# Flightcontroller.net
KiCad netlist of a schematic drawn in EAGLE
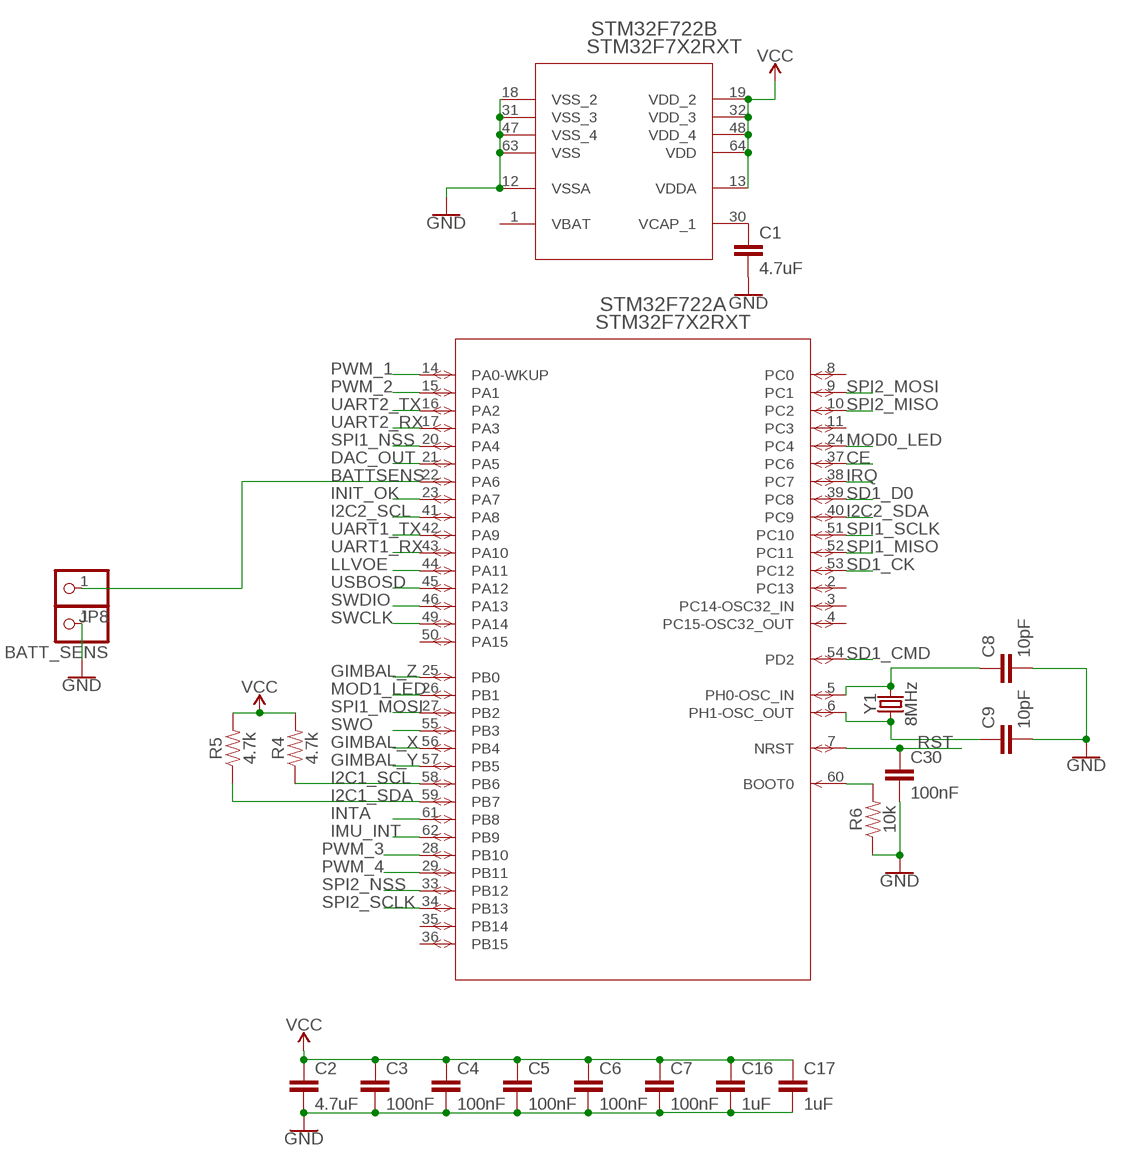
[diagram p0: schematic, sheet 1]
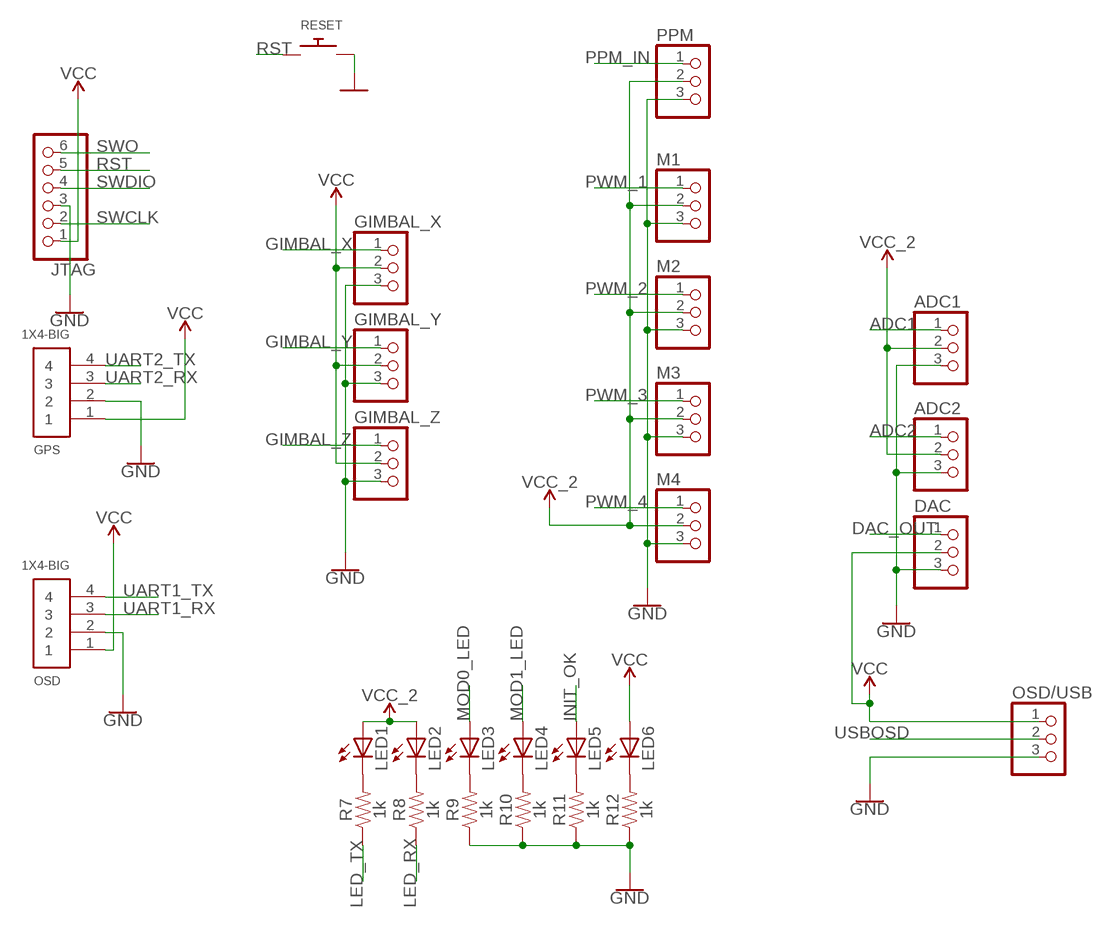
[diagram p1: schematic, sheet 2]
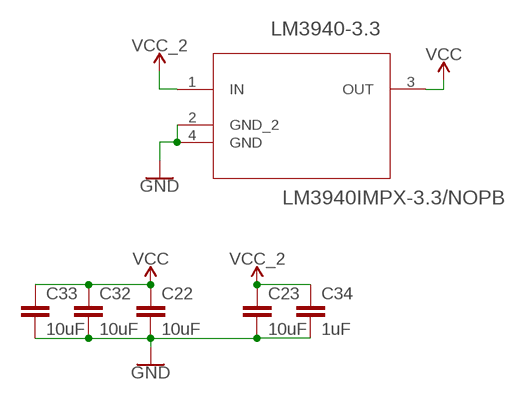
[diagram p2: schematic, sheet 3]
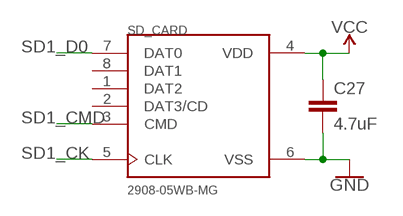
[diagram p3: schematic, sheet 4]
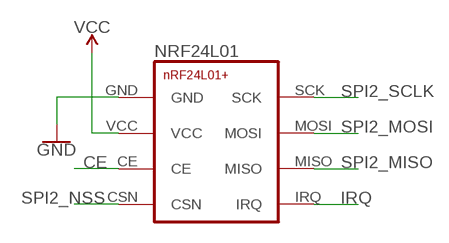
[diagram p4: schematic, sheet 5]
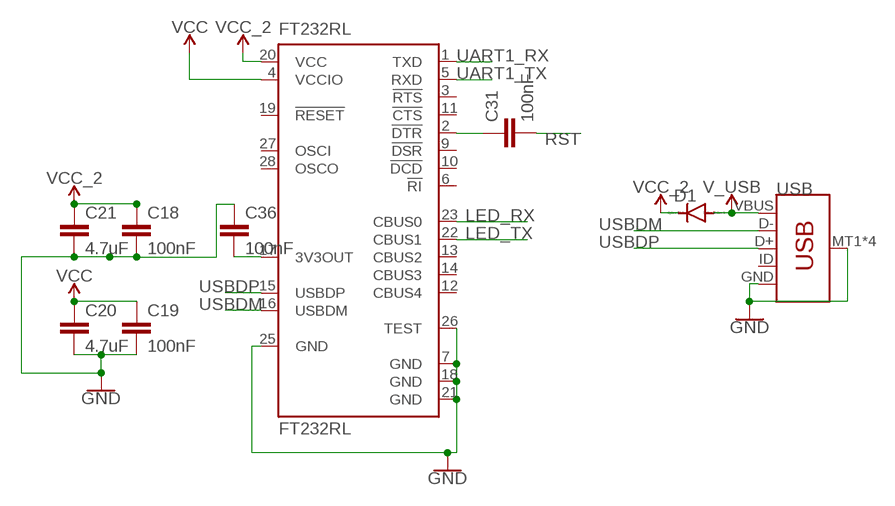
[diagram p5: schematic, sheet 6]
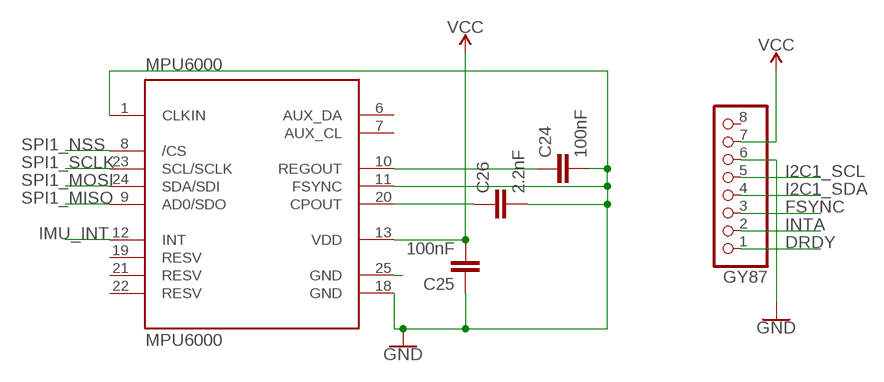
[diagram p6: schematic, sheet 7]
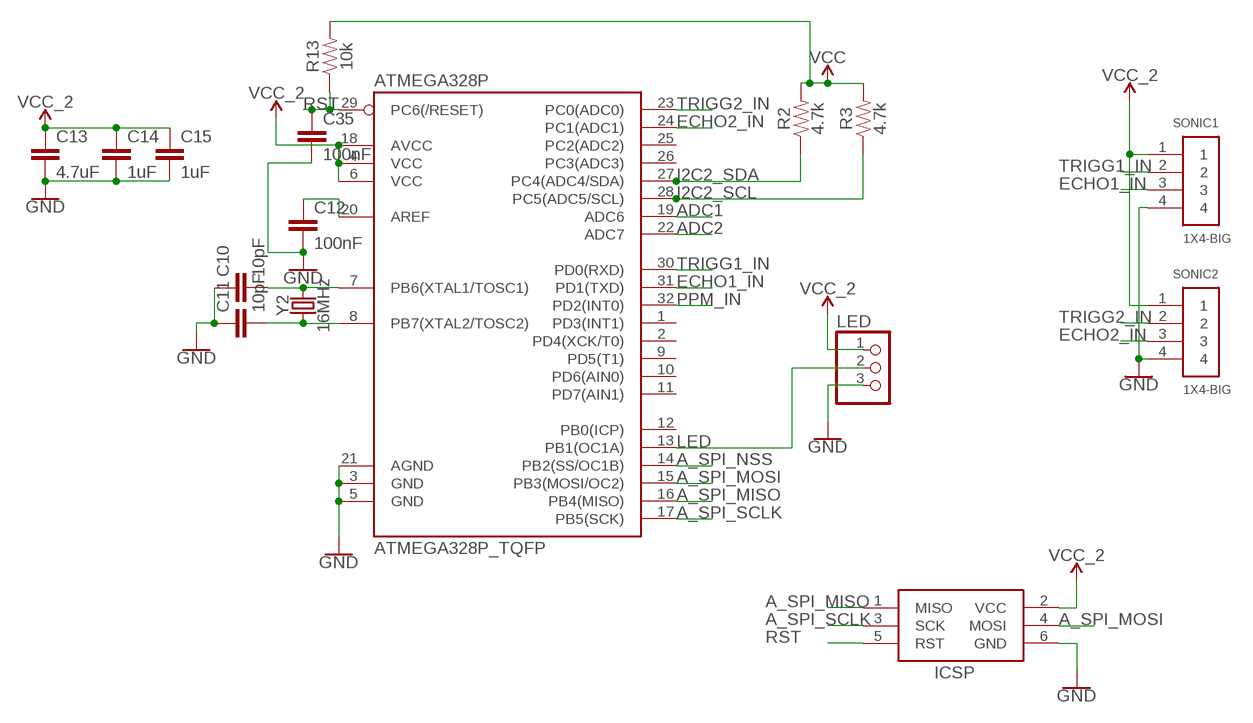
[diagram p7: schematic, sheet 8]
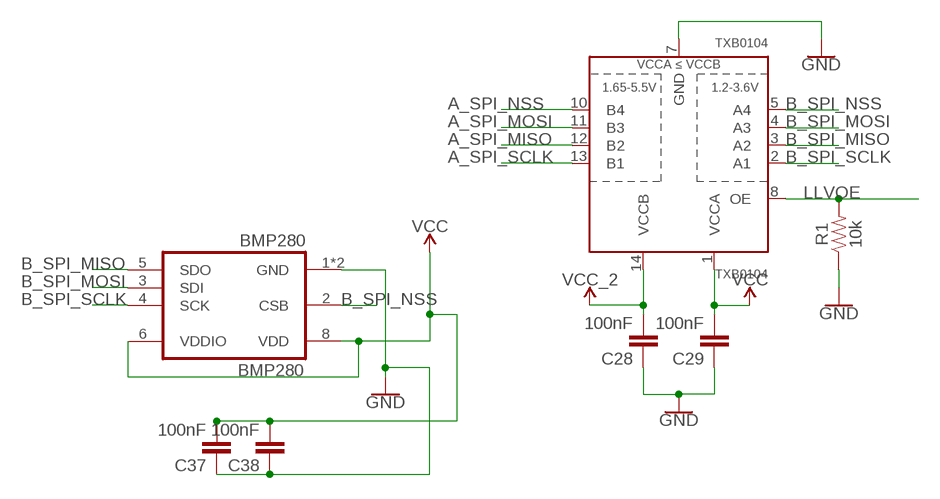
[diagram p8: schematic, sheet 9]
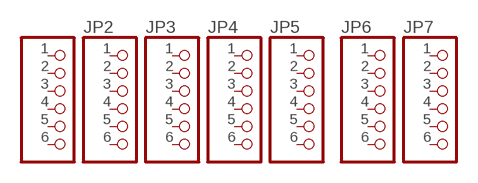
[diagram p9: schematic, sheet 10]

(export (version "E")
  (design (tool "Eeschema 10.0.6"))
  (components
    (comp (ref "C24")
      (value "100nF")
      (footprint "eagle-import:C0805")
      (libsource (lib "eagle-import") (part "C-EUC0805"))
    )
    (comp (ref "C25")
      (value "100nF")
      (footprint "eagle-import:C0805")
      (libsource (lib "eagle-import") (part "C-EUC0805"))
    )
    (comp (ref "C26")
      (value "2.2nF")
      (footprint "eagle-import:C0805")
      (libsource (lib "eagle-import") (part "C-EUC0805"))
    )
    (comp (ref "GY87")
      (value "PINHD-1X8CLEANBIG")
      (footprint "eagle-import:1X08-CLEANBIG")
      (libsource (lib "eagle-import") (part "PINHD-1X8CLEANBIG"))
    )
    (comp (ref "MPU6000")
      (value "MPU6000")
      (footprint "eagle-import:QFN50P400X400X95-25T265X275N")
      (libsource (lib "eagle-import") (part "MPU6000"))
    )
    (comp (ref "ADC1")
      (value "PINHD-1X3")
      (footprint "eagle-import:1X03")
      (libsource (lib "eagle-import") (part "PINHD-1X3"))
    )
    (comp (ref "ADC2")
      (value "PINHD-1X3")
      (footprint "eagle-import:1X03")
      (libsource (lib "eagle-import") (part "PINHD-1X3"))
    )
    (comp (ref "DAC")
      (value "PINHD-1X3")
      (footprint "eagle-import:1X03")
      (libsource (lib "eagle-import") (part "PINHD-1X3"))
    )
    (comp (ref "GIMBAL_X")
      (value "PINHD-1X3")
      (footprint "eagle-import:1X03")
      (libsource (lib "eagle-import") (part "PINHD-1X3"))
    )
    (comp (ref "GIMBAL_Y")
      (value "PINHD-1X3")
      (footprint "eagle-import:1X03")
      (libsource (lib "eagle-import") (part "PINHD-1X3"))
    )
    (comp (ref "GIMBAL_Z")
      (value "PINHD-1X3")
      (footprint "eagle-import:1X03")
      (libsource (lib "eagle-import") (part "PINHD-1X3"))
    )
    (comp (ref "GPS")
      (value "1X4-BIG")
      (footprint "eagle-import:1X04-BIG")
      (libsource (lib "eagle-import") (part "1X4-BIG"))
    )
    (comp (ref "JTAG")
      (value "PINHD-1X6")
      (footprint "eagle-import:1X06")
      (libsource (lib "eagle-import") (part "PINHD-1X6"))
    )
    (comp (ref "LED1")
      (value "LEDSMT1206")
      (footprint "eagle-import:1206")
      (libsource (lib "eagle-import") (part "LEDSMT1206"))
    )
    (comp (ref "LED2")
      (value "LEDSMT1206")
      (footprint "eagle-import:1206")
      (libsource (lib "eagle-import") (part "LEDSMT1206"))
    )
    (comp (ref "LED3")
      (value "LEDSMT1206")
      (footprint "eagle-import:1206")
      (libsource (lib "eagle-import") (part "LEDSMT1206"))
    )
    (comp (ref "LED4")
      (value "LEDSMT1206")
      (footprint "eagle-import:1206")
      (libsource (lib "eagle-import") (part "LEDSMT1206"))
    )
    (comp (ref "LED5")
      (value "LEDSMT1206")
      (footprint "eagle-import:1206")
      (libsource (lib "eagle-import") (part "LEDSMT1206"))
    )
    (comp (ref "LED6")
      (value "LEDSMT1206")
      (footprint "eagle-import:1206")
      (libsource (lib "eagle-import") (part "LEDSMT1206"))
    )
    (comp (ref "M1")
      (value "PINHD-1X3")
      (footprint "eagle-import:1X03")
      (libsource (lib "eagle-import") (part "PINHD-1X3"))
    )
    (comp (ref "M2")
      (value "PINHD-1X3")
      (footprint "eagle-import:1X03")
      (libsource (lib "eagle-import") (part "PINHD-1X3"))
    )
    (comp (ref "M3")
      (value "PINHD-1X3")
      (footprint "eagle-import:1X03")
      (libsource (lib "eagle-import") (part "PINHD-1X3"))
    )
    (comp (ref "M4")
      (value "PINHD-1X3")
      (footprint "eagle-import:1X03")
      (libsource (lib "eagle-import") (part "PINHD-1X3"))
    )
    (comp (ref "OSD")
      (value "1X4-BIG")
      (footprint "eagle-import:1X04-BIG")
      (libsource (lib "eagle-import") (part "1X4-BIG"))
    )
    (comp (ref "OSD/USB")
      (value "PINHD-1X3")
      (footprint "eagle-import:1X03")
      (libsource (lib "eagle-import") (part "PINHD-1X3"))
    )
    (comp (ref "PPM")
      (value "PINHD-1X3")
      (footprint "eagle-import:1X03")
      (libsource (lib "eagle-import") (part "PINHD-1X3"))
    )
    (comp (ref "R7")
      (value "1k")
      (footprint "eagle-import:0603")
      (libsource (lib "eagle-import") (part "10KOHM-0603-1/10W-1%"))
    )
    (comp (ref "R8")
      (value "1k")
      (footprint "eagle-import:0603")
      (libsource (lib "eagle-import") (part "10KOHM-0603-1/10W-1%"))
    )
    (comp (ref "R9")
      (value "1k")
      (footprint "eagle-import:0603")
      (libsource (lib "eagle-import") (part "10KOHM-0603-1/10W-1%"))
    )
    (comp (ref "R10")
      (value "1k")
      (footprint "eagle-import:0603")
      (libsource (lib "eagle-import") (part "10KOHM-0603-1/10W-1%"))
    )
    (comp (ref "R11")
      (value "1k")
      (footprint "eagle-import:0603")
      (libsource (lib "eagle-import") (part "10KOHM-0603-1/10W-1%"))
    )
    (comp (ref "R12")
      (value "1k")
      (footprint "eagle-import:0603")
      (libsource (lib "eagle-import") (part "10KOHM-0603-1/10W-1%"))
    )
    (comp (ref "RESET")
      (value "SWITCH_PUSHBUTTONC&K_KSS")
      (footprint "eagle-import:BTN_CK_KSS")
      (libsource (lib "eagle-import") (part "SWITCH_PUSHBUTTONC&K_KSS"))
    )
    (comp (ref "BATT_SENS")
      (value "PINHD-1X1")
      (footprint "eagle-import:1X01")
      (libsource (lib "eagle-import") (part "PINHD-1X1"))
    )
    (comp (ref "C1")
      (value "4.7uF")
      (footprint "eagle-import:C0805")
      (libsource (lib "eagle-import") (part "resistor_348_C-EUC0805"))
    )
    (comp (ref "C2")
      (value "4.7uF")
      (footprint "eagle-import:C0805")
      (libsource (lib "eagle-import") (part "resistor_348_C-EUC0805"))
    )
    (comp (ref "C3")
      (value "100nF")
      (footprint "eagle-import:C0805")
      (libsource (lib "eagle-import") (part "C-EUC0805"))
    )
    (comp (ref "C4")
      (value "100nF")
      (footprint "eagle-import:C0805")
      (libsource (lib "eagle-import") (part "C-EUC0805"))
    )
    (comp (ref "C5")
      (value "100nF")
      (footprint "eagle-import:C0805")
      (libsource (lib "eagle-import") (part "C-EUC0805"))
    )
    (comp (ref "C6")
      (value "100nF")
      (footprint "eagle-import:C0805")
      (libsource (lib "eagle-import") (part "C-EUC0805"))
    )
    (comp (ref "C7")
      (value "100nF")
      (footprint "eagle-import:C0805")
      (libsource (lib "eagle-import") (part "C-EUC0805"))
    )
    (comp (ref "C8")
      (value "10pF")
      (footprint "eagle-import:C0805")
      (libsource (lib "eagle-import") (part "C-EUC0805"))
    )
    (comp (ref "C9")
      (value "10pF")
      (footprint "eagle-import:C0805")
      (libsource (lib "eagle-import") (part "C-EUC0805"))
    )
    (comp (ref "C16")
      (value "1uF")
      (footprint "eagle-import:C0805")
      (libsource (lib "eagle-import") (part "C-EUC0805"))
    )
    (comp (ref "C17")
      (value "1uF")
      (footprint "eagle-import:C0805")
      (libsource (lib "eagle-import") (part "C-EUC0805"))
    )
    (comp (ref "C30")
      (value "100nF")
      (footprint "eagle-import:C0805")
      (libsource (lib "eagle-import") (part "C-EUC0805"))
    )
    (comp (ref "JP8")
      (value "PINHD-1X1")
      (footprint "eagle-import:1X01")
      (libsource (lib "eagle-import") (part "PINHD-1X1"))
    )
    (comp (ref "R4")
      (value "4.7k")
      (footprint "eagle-import:0603")
      (libsource (lib "eagle-import") (part "4.7KOHM-0603-1/10W-1%"))
    )
    (comp (ref "R5")
      (value "4.7k")
      (footprint "eagle-import:0603")
      (libsource (lib "eagle-import") (part "4.7KOHM-0603-1/10W-1%"))
    )
    (comp (ref "R6")
      (value "10k")
      (footprint "eagle-import:0603")
      (libsource (lib "eagle-import") (part "10KOHM-0603-1/10W-1%"))
    )
    (comp (ref "STM32F722")
      (value "STM32F7X2RXT")
      (footprint "eagle-import:LQFP64-10X10MM")
      (libsource (lib "eagle-import") (part "STM32F7X2RXT"))
    )
    (comp (ref "Y1")
      (value "8MHz")
      (footprint "eagle-import:CRYSTAL-SMD-5X3.2-4PAD")
      (libsource (lib "eagle-import") (part "CRYSTAL-8MHZSMD-5X3.2"))
    )
    (comp (ref "NRF24L01")
      (value "NRF24L01+")
      (footprint "eagle-import:NRF24L01+")
      (libsource (lib "eagle-import") (part "NRF24L01+"))
    )
    (comp (ref "C27")
      (value "4.7uF")
      (footprint "eagle-import:C0805")
      (libsource (lib "eagle-import") (part "resistor_348_C-EUC0805"))
    )
    (comp (ref "SD_CARD")
      (value "2908-05WB-MG")
      (footprint "eagle-import:3M_2908-05WB-MG")
      (fields (field (name "MF") "3M"))
      (libsource (lib "eagle-import") (part "2908-05WB-MG"))
    )
    (comp (ref "C18")
      (value "100nF")
      (footprint "eagle-import:C0805")
      (libsource (lib "eagle-import") (part "C-EUC0805"))
    )
    (comp (ref "C19")
      (value "100nF")
      (footprint "eagle-import:C0805")
      (libsource (lib "eagle-import") (part "C-EUC0805"))
    )
    (comp (ref "C20")
      (value "4.7uF")
      (footprint "eagle-import:C0805")
      (libsource (lib "eagle-import") (part "resistor_348_C-EUC0805"))
    )
    (comp (ref "C21")
      (value "4.7uF")
      (footprint "eagle-import:C0805")
      (libsource (lib "eagle-import") (part "resistor_348_C-EUC0805"))
    )
    (comp (ref "C31")
      (value "100nF")
      (footprint "eagle-import:C0805")
      (libsource (lib "eagle-import") (part "C-EUC0805"))
    )
    (comp (ref "C36")
      (value "100nF")
      (footprint "eagle-import:C0805")
      (libsource (lib "eagle-import") (part "C-EUC0805"))
    )
    (comp (ref "D1")
      (value "DIODE-DO214BA")
      (footprint "eagle-import:DO214BA")
      (libsource (lib "eagle-import") (part "DIODE-DO214BA"))
    )
    (comp (ref "FT232RL")
      (value "FT232RL")
      (footprint "eagle-import:SSOP28")
      (libsource (lib "eagle-import") (part "FT232RL"))
    )
    (comp (ref "USB")
      (value "USB_MICRO-B_SMT")
      (footprint "eagle-import:USB-MICROB")
      (libsource (lib "eagle-import") (part "USB_MICRO-B_SMT"))
    )
    (comp (ref "BMP280")
      (value "BMP280")
      (footprint "eagle-import:BMP280")
      (libsource (lib "eagle-import") (part "BMP280"))
    )
    (comp (ref "C28")
      (value "100nF")
      (footprint "eagle-import:C0805")
      (libsource (lib "eagle-import") (part "C-EUC0805"))
    )
    (comp (ref "C29")
      (value "100nF")
      (footprint "eagle-import:C0805")
      (libsource (lib "eagle-import") (part "C-EUC0805"))
    )
    (comp (ref "C37")
      (value "100nF")
      (footprint "eagle-import:C0805")
      (libsource (lib "eagle-import") (part "C-EUC0805"))
    )
    (comp (ref "C38")
      (value "100nF")
      (footprint "eagle-import:C0805")
      (libsource (lib "eagle-import") (part "C-EUC0805"))
    )
    (comp (ref "R1")
      (value "10k")
      (footprint "eagle-import:0603")
      (libsource (lib "eagle-import") (part "10KOHM-0603-1/10W-1%"))
    )
    (comp (ref "TXB0104")
      (value "TXB0104")
      (footprint "eagle-import:SO14")
      (libsource (lib "eagle-import") (part "TXB0104PWRSOIC14"))
    )
    (comp (ref "JP1")
      (value "PINHD-1X6")
      (footprint "eagle-import:1X06")
      (libsource (lib "eagle-import") (part "PINHD-1X6"))
    )
    (comp (ref "JP2")
      (value "PINHD-1X6")
      (footprint "eagle-import:1X06")
      (libsource (lib "eagle-import") (part "PINHD-1X6"))
    )
    (comp (ref "JP3")
      (value "PINHD-1X6")
      (footprint "eagle-import:1X06")
      (libsource (lib "eagle-import") (part "PINHD-1X6"))
    )
    (comp (ref "JP4")
      (value "PINHD-1X6")
      (footprint "eagle-import:1X06")
      (libsource (lib "eagle-import") (part "PINHD-1X6"))
    )
    (comp (ref "JP5")
      (value "PINHD-1X6")
      (footprint "eagle-import:1X06")
      (libsource (lib "eagle-import") (part "PINHD-1X6"))
    )
    (comp (ref "JP6")
      (value "PINHD-1X6")
      (footprint "eagle-import:1X06")
      (libsource (lib "eagle-import") (part "PINHD-1X6"))
    )
    (comp (ref "JP7")
      (value "PINHD-1X6")
      (footprint "eagle-import:1X06")
      (libsource (lib "eagle-import") (part "PINHD-1X6"))
    )
    (comp (ref "C22")
      (value "10uF")
      (footprint "eagle-import:C0805")
      (libsource (lib "eagle-import") (part "C-EUC0805"))
    )
    (comp (ref "C23")
      (value "10uF")
      (footprint "eagle-import:C0805")
      (libsource (lib "eagle-import") (part "C-EUC0805"))
    )
    (comp (ref "C32")
      (value "10uF")
      (footprint "eagle-import:C0805")
      (libsource (lib "eagle-import") (part "C-EUC0805"))
    )
    (comp (ref "C33")
      (value "10uF")
      (footprint "eagle-import:C0805")
      (libsource (lib "eagle-import") (part "C-EUC0805"))
    )
    (comp (ref "C34")
      (value "1uF")
      (footprint "eagle-import:C0805")
      (libsource (lib "eagle-import") (part "C-EUC0805"))
    )
    (comp (ref "LM3940-3.3")
      (value "LM3940IMPX-3.3/NOPB")
      (footprint "eagle-import:SOT230P696X180-4N")
      (fields (field (name "MF") "Texas Instruments"))
      (libsource (lib "eagle-import") (part "LM3940IMPX-3.3/NOPB"))
    )
    (comp (ref "ATMEGA328P")
      (value "ATMEGA328P_TQFP")
      (footprint "eagle-import:TQFP32-08")
      (libsource (lib "eagle-import") (part "ATMEGA328P_TQFP"))
    )
    (comp (ref "C10")
      (value "10pF")
      (footprint "eagle-import:C0805")
      (libsource (lib "eagle-import") (part "C-EUC0805"))
    )
    (comp (ref "C11")
      (value "10pF")
      (footprint "eagle-import:C0805")
      (libsource (lib "eagle-import") (part "C-EUC0805"))
    )
    (comp (ref "C12")
      (value "100nF")
      (footprint "eagle-import:C0805")
      (libsource (lib "eagle-import") (part "C-EUC0805"))
    )
    (comp (ref "C13")
      (value "4.7uF")
      (footprint "eagle-import:C0805")
      (libsource (lib "eagle-import") (part "resistor_348_C-EUC0805"))
    )
    (comp (ref "C14")
      (value "1uF")
      (footprint "eagle-import:C0805")
      (libsource (lib "eagle-import") (part "C-EUC0805"))
    )
    (comp (ref "C15")
      (value "1uF")
      (footprint "eagle-import:C0805")
      (libsource (lib "eagle-import") (part "C-EUC0805"))
    )
    (comp (ref "C35")
      (value "100nF")
      (footprint "eagle-import:C0805")
      (libsource (lib "eagle-import") (part "C-EUC0805"))
    )
    (comp (ref "ICSP")
      (value "AVRISP-6")
      (footprint "eagle-import:AVRISP")
      (libsource (lib "eagle-import") (part "AVRISP-6"))
    )
    (comp (ref "LED")
      (value "PINHD-1X3")
      (footprint "eagle-import:1X03")
      (libsource (lib "eagle-import") (part "PINHD-1X3"))
    )
    (comp (ref "R2")
      (value "4.7k")
      (footprint "eagle-import:0603")
      (libsource (lib "eagle-import") (part "4.7KOHM-0603-1/10W-1%"))
    )
    (comp (ref "R3")
      (value "4.7k")
      (footprint "eagle-import:0603")
      (libsource (lib "eagle-import") (part "4.7KOHM-0603-1/10W-1%"))
    )
    (comp (ref "R13")
      (value "10k")
      (footprint "eagle-import:0603")
      (libsource (lib "eagle-import") (part "4.7KOHM-0603-1/10W-1%"))
    )
    (comp (ref "SONIC1")
      (value "1X4-BIG")
      (footprint "eagle-import:1X04-BIG")
      (libsource (lib "eagle-import") (part "1X4-BIG"))
    )
    (comp (ref "SONIC2")
      (value "1X4-BIG")
      (footprint "eagle-import:1X04-BIG")
      (libsource (lib "eagle-import") (part "1X4-BIG"))
    )
    (comp (ref "Y2")
      (value "16MHz")
      (footprint "eagle-import:CRYSTAL-SMD-5X3.2-4PAD")
      (libsource (lib "eagle-import") (part "CRYSTAL-16MHZSMD-5X3.2"))
    )
  )
  (nets
    (net (code "1") (name "ADC1") (class "Default")
      (node (ref "ADC1") (pin "1") (pinfunction "1_1") (pintype "passive"))
      (node (ref "ATMEGA328P") (pin "19") (pinfunction "ADC6_19") (pintype "bidirectional"))
    )
    (net (code "2") (name "ADC2") (class "Default")
      (node (ref "ADC2") (pin "1") (pinfunction "1_1") (pintype "passive"))
      (node (ref "ATMEGA328P") (pin "22") (pinfunction "ADC7_22") (pintype "bidirectional"))
    )
    (net (code "3") (name "A_SPI_MISO") (class "Default")
      (node (ref "ATMEGA328P") (pin "16") (pinfunction "PB4(MISO)_16") (pintype "bidirectional"))
      (node (ref "ICSP") (pin "1") (pinfunction "MISO_1") (pintype "input"))
      (node (ref "TXB0104") (pin "12") (pinfunction "B2_12") (pintype "bidirectional"))
    )
    (net (code "4") (name "A_SPI_MOSI") (class "Default")
      (node (ref "ATMEGA328P") (pin "15") (pinfunction "PB3(MOSI/OC2)_15") (pintype "bidirectional"))
      (node (ref "ICSP") (pin "4") (pinfunction "MOSI_4") (pintype "output"))
      (node (ref "TXB0104") (pin "11") (pinfunction "B3_11") (pintype "bidirectional"))
    )
    (net (code "5") (name "A_SPI_NSS") (class "Default")
      (node (ref "ATMEGA328P") (pin "14") (pinfunction "PB2(SS/OC1B)_14") (pintype "bidirectional"))
      (node (ref "TXB0104") (pin "10") (pinfunction "B4_10") (pintype "bidirectional"))
    )
    (net (code "6") (name "A_SPI_SCLK") (class "Default")
      (node (ref "ATMEGA328P") (pin "17") (pinfunction "PB5(SCK)_17") (pintype "bidirectional"))
      (node (ref "ICSP") (pin "3") (pinfunction "SCK_3") (pintype "output"))
      (node (ref "TXB0104") (pin "13") (pinfunction "B1_13") (pintype "bidirectional"))
    )
    (net (code "7") (name "BATTSENS") (class "Default")
      (node (ref "JP8") (pin "1") (pinfunction "1_1") (pintype "passive"))
      (node (ref "STM32F722") (pin "22") (pinfunction "PA6_22") (pintype "bidirectional"))
    )
    (net (code "8") (name "B_SPI_MISO") (class "Default")
      (node (ref "BMP280") (pin "5") (pinfunction "SDO_5") (pintype "input"))
      (node (ref "TXB0104") (pin "3") (pinfunction "A2_3") (pintype "bidirectional"))
    )
    (net (code "9") (name "B_SPI_MOSI") (class "Default")
      (node (ref "BMP280") (pin "3") (pinfunction "SDI_3") (pintype "bidirectional"))
      (node (ref "TXB0104") (pin "4") (pinfunction "A3_4") (pintype "bidirectional"))
    )
    (net (code "10") (name "B_SPI_NSS") (class "Default")
      (node (ref "BMP280") (pin "2") (pinfunction "CSB_2") (pintype "input"))
      (node (ref "TXB0104") (pin "5") (pinfunction "A4_5") (pintype "bidirectional"))
    )
    (net (code "11") (name "B_SPI_SCLK") (class "Default")
      (node (ref "BMP280") (pin "4") (pinfunction "SCK_4") (pintype "bidirectional"))
      (node (ref "TXB0104") (pin "2") (pinfunction "A1_2") (pintype "bidirectional"))
    )
    (net (code "12") (name "CE") (class "Default")
      (node (ref "NRF24L01") (pin "CE") (pinfunction "CE_CE") (pintype "bidirectional"))
      (node (ref "STM32F722") (pin "37") (pinfunction "PC6_37") (pintype "bidirectional"))
    )
    (net (code "13") (name "DAC_OUT") (class "Default")
      (node (ref "DAC") (pin "1") (pinfunction "1_1") (pintype "passive"))
      (node (ref "STM32F722") (pin "21") (pinfunction "PA5_21") (pintype "bidirectional"))
    )
    (net (code "14") (name "DRDY") (class "Default")
      (node (ref "GY87") (pin "1") (pinfunction "1_1") (pintype "passive"))
    )
    (net (code "15") (name "ECHO1_IN") (class "Default")
      (node (ref "ATMEGA328P") (pin "31") (pinfunction "PD1(TXD)_31") (pintype "bidirectional"))
      (node (ref "SONIC1") (pin "3") (pinfunction "3_3") (pintype "bidirectional"))
    )
    (net (code "16") (name "ECHO2_IN") (class "Default")
      (node (ref "ATMEGA328P") (pin "24") (pinfunction "PC1(ADC1)_24") (pintype "bidirectional"))
      (node (ref "SONIC2") (pin "3") (pinfunction "3_3") (pintype "bidirectional"))
    )
    (net (code "17") (name "FSYNC") (class "Default")
      (node (ref "GY87") (pin "3") (pinfunction "3_3") (pintype "passive"))
    )
    (net (code "18") (name "GIMBAL_X") (class "Default")
      (node (ref "GIMBAL_X") (pin "1") (pinfunction "1_1") (pintype "passive"))
      (node (ref "STM32F722") (pin "56") (pinfunction "PB4_56") (pintype "bidirectional"))
    )
    (net (code "19") (name "GIMBAL_Y") (class "Default")
      (node (ref "GIMBAL_Y") (pin "1") (pinfunction "1_1") (pintype "passive"))
      (node (ref "STM32F722") (pin "57") (pinfunction "PB5_57") (pintype "bidirectional"))
    )
    (net (code "20") (name "GIMBAL_Z") (class "Default")
      (node (ref "GIMBAL_Z") (pin "1") (pinfunction "1_1") (pintype "passive"))
      (node (ref "STM32F722") (pin "25") (pinfunction "PB0_25") (pintype "bidirectional"))
    )
    (net (code "21") (name "GND") (class "Default")
      (node (ref "ADC1") (pin "3") (pinfunction "3_3") (pintype "passive"))
      (node (ref "ADC2") (pin "3") (pinfunction "3_3") (pintype "passive"))
      (node (ref "ATMEGA328P") (pin "21") (pinfunction "AGND_21") (pintype "bidirectional"))
      (node (ref "ATMEGA328P") (pin "3") (pinfunction "GND_3") (pintype "bidirectional"))
      (node (ref "ATMEGA328P") (pin "5") (pinfunction "GND_5") (pintype "bidirectional"))
      (node (ref "BATT_SENS") (pin "1") (pinfunction "1_1") (pintype "passive"))
      (node (ref "BMP280") (pin "1") (pinfunction "GND_1") (pintype "power_in"))
      (node (ref "BMP280") (pin "7") (pinfunction "GND_7") (pintype "power_in"))
      (node (ref "C1") (pin "2") (pinfunction "2_2") (pintype "passive"))
      (node (ref "C10") (pin "1") (pinfunction "1_1") (pintype "passive"))
      (node (ref "C11") (pin "1") (pinfunction "1_1") (pintype "passive"))
      (node (ref "C12") (pin "2") (pinfunction "2_2") (pintype "passive"))
      (node (ref "C13") (pin "2") (pinfunction "2_2") (pintype "passive"))
      (node (ref "C14") (pin "2") (pinfunction "2_2") (pintype "passive"))
      (node (ref "C15") (pin "2") (pinfunction "2_2") (pintype "passive"))
      (node (ref "C16") (pin "2") (pinfunction "2_2") (pintype "passive"))
      (node (ref "C17") (pin "2") (pinfunction "2_2") (pintype "passive"))
      (node (ref "C18") (pin "2") (pinfunction "2_2") (pintype "passive"))
      (node (ref "C19") (pin "2") (pinfunction "2_2") (pintype "passive"))
      (node (ref "C2") (pin "2") (pinfunction "2_2") (pintype "passive"))
      (node (ref "C20") (pin "2") (pinfunction "2_2") (pintype "passive"))
      (node (ref "C21") (pin "2") (pinfunction "2_2") (pintype "passive"))
      (node (ref "C22") (pin "2") (pinfunction "2_2") (pintype "passive"))
      (node (ref "C23") (pin "2") (pinfunction "2_2") (pintype "passive"))
      (node (ref "C24") (pin "2") (pinfunction "2_2") (pintype "passive"))
      (node (ref "C25") (pin "1") (pinfunction "1_1") (pintype "passive"))
      (node (ref "C26") (pin "2") (pinfunction "2_2") (pintype "passive"))
      (node (ref "C27") (pin "2") (pinfunction "2_2") (pintype "passive"))
      (node (ref "C28") (pin "1") (pinfunction "1_1") (pintype "passive"))
      (node (ref "C29") (pin "1") (pinfunction "1_1") (pintype "passive"))
      (node (ref "C3") (pin "2") (pinfunction "2_2") (pintype "passive"))
      (node (ref "C30") (pin "2") (pinfunction "2_2") (pintype "passive"))
      (node (ref "C32") (pin "2") (pinfunction "2_2") (pintype "passive"))
      (node (ref "C33") (pin "2") (pinfunction "2_2") (pintype "passive"))
      (node (ref "C34") (pin "2") (pinfunction "2_2") (pintype "passive"))
      (node (ref "C35") (pin "2") (pinfunction "2_2") (pintype "passive"))
      (node (ref "C36") (pin "1") (pinfunction "1_1") (pintype "passive"))
      (node (ref "C37") (pin "1") (pinfunction "1_1") (pintype "passive"))
      (node (ref "C38") (pin "1") (pinfunction "1_1") (pintype "passive"))
      (node (ref "C4") (pin "2") (pinfunction "2_2") (pintype "passive"))
      (node (ref "C5") (pin "2") (pinfunction "2_2") (pintype "passive"))
      (node (ref "C6") (pin "2") (pinfunction "2_2") (pintype "passive"))
      (node (ref "C7") (pin "2") (pinfunction "2_2") (pintype "passive"))
      (node (ref "C8") (pin "2") (pinfunction "2_2") (pintype "passive"))
      (node (ref "C9") (pin "2") (pinfunction "2_2") (pintype "passive"))
      (node (ref "DAC") (pin "3") (pinfunction "3_3") (pintype "passive"))
      (node (ref "FT232RL") (pin "18") (pinfunction "GND_18") (pintype "power_in"))
      (node (ref "FT232RL") (pin "21") (pinfunction "GND_21") (pintype "power_in"))
      (node (ref "FT232RL") (pin "25") (pinfunction "GND_25") (pintype "power_in"))
      (node (ref "FT232RL") (pin "26") (pinfunction "TEST_26") (pintype "input"))
      (node (ref "FT232RL") (pin "7") (pinfunction "GND_7") (pintype "power_in"))
      (node (ref "GIMBAL_X") (pin "3") (pinfunction "3_3") (pintype "passive"))
      (node (ref "GIMBAL_Y") (pin "3") (pinfunction "3_3") (pintype "passive"))
      (node (ref "GIMBAL_Z") (pin "3") (pinfunction "3_3") (pintype "passive"))
      (node (ref "GPS") (pin "2") (pinfunction "2_2") (pintype "bidirectional"))
      (node (ref "GY87") (pin "6") (pinfunction "6_6") (pintype "passive"))
      (node (ref "ICSP") (pin "6") (pinfunction "GND_6") (pintype "power_in"))
      (node (ref "JTAG") (pin "3") (pinfunction "3_3") (pintype "passive"))
      (node (ref "LED") (pin "3") (pinfunction "3_3") (pintype "passive"))
      (node (ref "LM3940-3.3") (pin "2") (pinfunction "GND_2_2") (pintype "passive"))
      (node (ref "LM3940-3.3") (pin "4") (pinfunction "GND_4") (pintype "passive"))
      (node (ref "M1") (pin "3") (pinfunction "3_3") (pintype "passive"))
      (node (ref "M2") (pin "3") (pinfunction "3_3") (pintype "passive"))
      (node (ref "M3") (pin "3") (pinfunction "3_3") (pintype "passive"))
      (node (ref "M4") (pin "3") (pinfunction "3_3") (pintype "passive"))
      (node (ref "MPU6000") (pin "1") (pinfunction "CLKIN_1") (pintype "input"))
      (node (ref "MPU6000") (pin "11") (pinfunction "FSYNC_11") (pintype "input"))
      (node (ref "MPU6000") (pin "18") (pinfunction "GND_18") (pintype "power_in"))
      (node (ref "NRF24L01") (pin "GND") (pinfunction "GND_GND") (pintype "power_in"))
      (node (ref "OSD") (pin "2") (pinfunction "2_2") (pintype "bidirectional"))
      (node (ref "OSD/USB") (pin "3") (pinfunction "3_3") (pintype "passive"))
      (node (ref "PPM") (pin "3") (pinfunction "3_3") (pintype "passive"))
      (node (ref "R1") (pin "1") (pinfunction "1_1") (pintype "passive"))
      (node (ref "R10") (pin "1") (pinfunction "1_1") (pintype "passive"))
      (node (ref "R11") (pin "1") (pinfunction "1_1") (pintype "passive"))
      (node (ref "R12") (pin "1") (pinfunction "1_1") (pintype "passive"))
      (node (ref "R6") (pin "1") (pinfunction "1_1") (pintype "passive"))
      (node (ref "R9") (pin "1") (pinfunction "1_1") (pintype "passive"))
      (node (ref "RESET") (pin "P$2") (pinfunction "P$2_P$2") (pintype "passive"))
      (node (ref "SD_CARD") (pin "6") (pinfunction "VSS_6") (pintype "power_in"))
      (node (ref "SONIC1") (pin "4") (pinfunction "4_4") (pintype "bidirectional"))
      (node (ref "SONIC2") (pin "4") (pinfunction "4_4") (pintype "bidirectional"))
      (node (ref "STM32F722") (pin "12") (pinfunction "VSSA_12") (pintype "power_in"))
      (node (ref "STM32F722") (pin "18") (pinfunction "VSS_2_18") (pintype "power_in"))
      (node (ref "STM32F722") (pin "31") (pinfunction "VSS_3_31") (pintype "power_in"))
      (node (ref "STM32F722") (pin "47") (pinfunction "VSS_4_47") (pintype "power_in"))
      (node (ref "STM32F722") (pin "63") (pinfunction "VSS_63") (pintype "power_in"))
      (node (ref "TXB0104") (pin "7") (pinfunction "GND_7") (pintype "bidirectional"))
      (node (ref "USB") (pin "GND") (pinfunction "GND_GND") (pintype "power_in"))
      (node (ref "USB") (pin "MT1") (pinfunction "SHIELD_MT1") (pintype "bidirectional"))
      (node (ref "USB") (pin "MT2") (pinfunction "SHIELD_MT2") (pintype "bidirectional"))
      (node (ref "USB") (pin "P$1") (pinfunction "SHIELD_P$1") (pintype "bidirectional"))
      (node (ref "USB") (pin "P$2") (pinfunction "SHIELD_P$2") (pintype "bidirectional"))
    )
    (net (code "22") (name "I2C1_SCL") (class "Default")
      (node (ref "GY87") (pin "5") (pinfunction "5_5") (pintype "passive"))
      (node (ref "R4") (pin "1") (pinfunction "1_1") (pintype "passive"))
      (node (ref "STM32F722") (pin "58") (pinfunction "PB6_58") (pintype "bidirectional"))
    )
    (net (code "23") (name "I2C1_SDA") (class "Default")
      (node (ref "GY87") (pin "4") (pinfunction "4_4") (pintype "passive"))
      (node (ref "R5") (pin "1") (pinfunction "1_1") (pintype "passive"))
      (node (ref "STM32F722") (pin "59") (pinfunction "PB7_59") (pintype "bidirectional"))
    )
    (net (code "24") (name "I2C2_SCL") (class "Default")
      (node (ref "ATMEGA328P") (pin "28") (pinfunction "PC5(ADC5/SCL)_28") (pintype "bidirectional"))
      (node (ref "R3") (pin "1") (pinfunction "1_1") (pintype "passive"))
      (node (ref "STM32F722") (pin "41") (pinfunction "PA8_41") (pintype "bidirectional"))
    )
    (net (code "25") (name "I2C2_SDA") (class "Default")
      (node (ref "ATMEGA328P") (pin "27") (pinfunction "PC4(ADC4/SDA)_27") (pintype "bidirectional"))
      (node (ref "R2") (pin "1") (pinfunction "1_1") (pintype "passive"))
      (node (ref "STM32F722") (pin "40") (pinfunction "PC9_40") (pintype "bidirectional"))
    )
    (net (code "26") (name "IMU_INT") (class "Default")
      (node (ref "MPU6000") (pin "12") (pinfunction "INT_12") (pintype "open_collector"))
      (node (ref "STM32F722") (pin "62") (pinfunction "PB9_62") (pintype "bidirectional"))
    )
    (net (code "27") (name "INIT_OK") (class "Default")
      (node (ref "LED5") (pin "A") (pinfunction "A_A") (pintype "passive"))
      (node (ref "STM32F722") (pin "23") (pinfunction "PA7_23") (pintype "bidirectional"))
    )
    (net (code "28") (name "INTA") (class "Default")
      (node (ref "GY87") (pin "2") (pinfunction "2_2") (pintype "passive"))
      (node (ref "STM32F722") (pin "61") (pinfunction "PB8_61") (pintype "bidirectional"))
    )
    (net (code "29") (name "IRQ") (class "Default")
      (node (ref "NRF24L01") (pin "IRQ") (pinfunction "IRQ_IRQ") (pintype "bidirectional"))
      (node (ref "STM32F722") (pin "38") (pinfunction "PC7_38") (pintype "bidirectional"))
    )
    (net (code "30") (name "LED") (class "Default")
      (node (ref "ATMEGA328P") (pin "13") (pinfunction "PB1(OC1A)_13") (pintype "bidirectional"))
      (node (ref "LED") (pin "2") (pinfunction "2_2") (pintype "passive"))
    )
    (net (code "31") (name "LED_RX") (class "Default")
      (node (ref "FT232RL") (pin "23") (pinfunction "CBUS0_23") (pintype "bidirectional"))
      (node (ref "R8") (pin "1") (pinfunction "1_1") (pintype "passive"))
    )
    (net (code "32") (name "LED_TX") (class "Default")
      (node (ref "FT232RL") (pin "22") (pinfunction "CBUS1_22") (pintype "bidirectional"))
      (node (ref "R7") (pin "1") (pinfunction "1_1") (pintype "passive"))
    )
    (net (code "33") (name "LLVOE") (class "Default")
      (node (ref "R1") (pin "2") (pinfunction "2_2") (pintype "passive"))
      (node (ref "STM32F722") (pin "44") (pinfunction "PA11_44") (pintype "bidirectional"))
      (node (ref "TXB0104") (pin "8") (pinfunction "OE_8") (pintype "bidirectional"))
    )
    (net (code "34") (name "MOD0_LED") (class "Default")
      (node (ref "LED3") (pin "A") (pinfunction "A_A") (pintype "passive"))
      (node (ref "STM32F722") (pin "24") (pinfunction "PC4_24") (pintype "bidirectional"))
    )
    (net (code "35") (name "MOD1_LED") (class "Default")
      (node (ref "LED4") (pin "A") (pinfunction "A_A") (pintype "passive"))
      (node (ref "STM32F722") (pin "26") (pinfunction "PB1_26") (pintype "bidirectional"))
    )
    (net (code "36") (name "Net-(ATMEGA328P-AREF)") (class "Default")
      (node (ref "ATMEGA328P") (pin "20") (pinfunction "AREF_20") (pintype "bidirectional"))
      (node (ref "C12") (pin "1") (pinfunction "1_1") (pintype "passive"))
    )
    (net (code "37") (name "Net-(ATMEGA328P-PB6(XTAL1{slash}TOSC1))") (class "Default")
      (node (ref "ATMEGA328P") (pin "7") (pinfunction "PB6(XTAL1/TOSC1)_7") (pintype "bidirectional"))
      (node (ref "C10") (pin "2") (pinfunction "2_2") (pintype "passive"))
      (node (ref "Y2") (pin "3") (pinfunction "2_3") (pintype "passive"))
    )
    (net (code "38") (name "Net-(ATMEGA328P-PB7(XTAL2{slash}TOSC2))") (class "Default")
      (node (ref "ATMEGA328P") (pin "8") (pinfunction "PB7(XTAL2/TOSC2)_8") (pintype "bidirectional"))
      (node (ref "C11") (pin "2") (pinfunction "2_2") (pintype "passive"))
      (node (ref "Y2") (pin "1") (pinfunction "1_1") (pintype "passive"))
    )
    (net (code "39") (name "Net-(FT232RL-3V3OUT)") (class "Default")
      (node (ref "C36") (pin "2") (pinfunction "2_2") (pintype "passive"))
      (node (ref "FT232RL") (pin "17") (pinfunction "3V3OUT_17") (pintype "output"))
    )
    (net (code "40") (name "Net-(FT232RL-~{DTR})") (class "Default")
      (node (ref "C31") (pin "1") (pinfunction "1_1") (pintype "passive"))
      (node (ref "FT232RL") (pin "2") (pinfunction "~{DTR}_2") (pintype "output"))
    )
    (net (code "41") (name "Net-(LED1-PadC)") (class "Default")
      (node (ref "LED1") (pin "C") (pinfunction "C_C") (pintype "passive"))
      (node (ref "R7") (pin "2") (pinfunction "2_2") (pintype "passive"))
    )
    (net (code "42") (name "Net-(LED2-PadC)") (class "Default")
      (node (ref "LED2") (pin "C") (pinfunction "C_C") (pintype "passive"))
      (node (ref "R8") (pin "2") (pinfunction "2_2") (pintype "passive"))
    )
    (net (code "43") (name "Net-(LED3-PadC)") (class "Default")
      (node (ref "LED3") (pin "C") (pinfunction "C_C") (pintype "passive"))
      (node (ref "R9") (pin "2") (pinfunction "2_2") (pintype "passive"))
    )
    (net (code "44") (name "Net-(LED4-PadC)") (class "Default")
      (node (ref "LED4") (pin "C") (pinfunction "C_C") (pintype "passive"))
      (node (ref "R10") (pin "2") (pinfunction "2_2") (pintype "passive"))
    )
    (net (code "45") (name "Net-(LED5-PadC)") (class "Default")
      (node (ref "LED5") (pin "C") (pinfunction "C_C") (pintype "passive"))
      (node (ref "R11") (pin "2") (pinfunction "2_2") (pintype "passive"))
    )
    (net (code "46") (name "Net-(LED6-PadC)") (class "Default")
      (node (ref "LED6") (pin "C") (pinfunction "C_C") (pintype "passive"))
      (node (ref "R12") (pin "2") (pinfunction "2_2") (pintype "passive"))
    )
    (net (code "47") (name "Net-(MPU6000A-CPOUT)") (class "Default")
      (node (ref "C26") (pin "1") (pinfunction "1_1") (pintype "passive"))
      (node (ref "MPU6000") (pin "20") (pinfunction "CPOUT_20") (pintype "output"))
    )
    (net (code "48") (name "Net-(MPU6000A-REGOUT)") (class "Default")
      (node (ref "C24") (pin "1") (pinfunction "1_1") (pintype "passive"))
      (node (ref "MPU6000") (pin "10") (pinfunction "REGOUT_10") (pintype "output"))
    )
    (net (code "49") (name "Net-(STM32F722A-BOOT0)") (class "Default")
      (node (ref "R6") (pin "2") (pinfunction "2_2") (pintype "passive"))
      (node (ref "STM32F722") (pin "60") (pinfunction "BOOT0_60") (pintype "input"))
    )
    (net (code "50") (name "Net-(STM32F722A-PH0-OSC_IN)") (class "Default")
      (node (ref "C8") (pin "1") (pinfunction "1_1") (pintype "passive"))
      (node (ref "STM32F722") (pin "5") (pinfunction "PH0-OSC_IN_5") (pintype "bidirectional"))
      (node (ref "Y1") (pin "3") (pinfunction "2_3") (pintype "passive"))
    )
    (net (code "51") (name "Net-(STM32F722A-PH1-OSC_OUT)") (class "Default")
      (node (ref "C9") (pin "1") (pinfunction "1_1") (pintype "passive"))
      (node (ref "STM32F722") (pin "6") (pinfunction "PH1-OSC_OUT_6") (pintype "bidirectional"))
      (node (ref "Y1") (pin "1") (pinfunction "1_1") (pintype "passive"))
    )
    (net (code "52") (name "Net-(STM32F722B-VCAP_1)") (class "Default")
      (node (ref "C1") (pin "1") (pinfunction "1_1") (pintype "passive"))
      (node (ref "STM32F722") (pin "30") (pinfunction "VCAP_1_30") (pintype "power_in"))
    )
    (net (code "53") (name "PPM_IN") (class "Default")
      (node (ref "ATMEGA328P") (pin "32") (pinfunction "PD2(INT0)_32") (pintype "bidirectional"))
      (node (ref "PPM") (pin "1") (pinfunction "1_1") (pintype "passive"))
    )
    (net (code "54") (name "PWM_1") (class "Default")
      (node (ref "M1") (pin "1") (pinfunction "1_1") (pintype "passive"))
      (node (ref "STM32F722") (pin "14") (pinfunction "PA0-WKUP_14") (pintype "bidirectional"))
    )
    (net (code "55") (name "PWM_2") (class "Default")
      (node (ref "M2") (pin "1") (pinfunction "1_1") (pintype "passive"))
      (node (ref "STM32F722") (pin "15") (pinfunction "PA1_15") (pintype "bidirectional"))
    )
    (net (code "56") (name "PWM_3") (class "Default")
      (node (ref "M3") (pin "1") (pinfunction "1_1") (pintype "passive"))
      (node (ref "STM32F722") (pin "28") (pinfunction "PB10_28") (pintype "bidirectional"))
    )
    (net (code "57") (name "PWM_4") (class "Default")
      (node (ref "M4") (pin "1") (pinfunction "1_1") (pintype "passive"))
      (node (ref "STM32F722") (pin "29") (pinfunction "PB11_29") (pintype "bidirectional"))
    )
    (net (code "58") (name "RST") (class "Default")
      (node (ref "ATMEGA328P") (pin "29") (pinfunction "PC6(/RESET)_29") (pintype "bidirectional"))
      (node (ref "C30") (pin "1") (pinfunction "1_1") (pintype "passive"))
      (node (ref "C31") (pin "2") (pinfunction "2_2") (pintype "passive"))
      (node (ref "C35") (pin "1") (pinfunction "1_1") (pintype "passive"))
      (node (ref "ICSP") (pin "5") (pinfunction "RST_5") (pintype "output"))
      (node (ref "JTAG") (pin "5") (pinfunction "5_5") (pintype "passive"))
      (node (ref "R13") (pin "1") (pinfunction "1_1") (pintype "passive"))
      (node (ref "RESET") (pin "P$1") (pinfunction "P$1_P$1") (pintype "passive"))
      (node (ref "STM32F722") (pin "7") (pinfunction "NRST_7") (pintype "bidirectional"))
    )
    (net (code "59") (name "SD1_CK") (class "Default")
      (node (ref "SD_CARD") (pin "5") (pinfunction "CLK_5") (pintype "bidirectional"))
      (node (ref "STM32F722") (pin "53") (pinfunction "PC12_53") (pintype "bidirectional"))
    )
    (net (code "60") (name "SD1_CMD") (class "Default")
      (node (ref "SD_CARD") (pin "3") (pinfunction "CMD_3") (pintype "bidirectional"))
      (node (ref "STM32F722") (pin "54") (pinfunction "PD2_54") (pintype "bidirectional"))
    )
    (net (code "61") (name "SD1_D0") (class "Default")
      (node (ref "SD_CARD") (pin "7") (pinfunction "DAT0_7") (pintype "bidirectional"))
      (node (ref "STM32F722") (pin "39") (pinfunction "PC8_39") (pintype "bidirectional"))
    )
    (net (code "62") (name "SPI1_MISO") (class "Default")
      (node (ref "MPU6000") (pin "9") (pinfunction "AD0/SDO_9") (pintype "bidirectional"))
      (node (ref "STM32F722") (pin "52") (pinfunction "PC11_52") (pintype "bidirectional"))
    )
    (net (code "63") (name "SPI1_MOSI") (class "Default")
      (node (ref "MPU6000") (pin "24") (pinfunction "SDA/SDI_24") (pintype "bidirectional"))
      (node (ref "STM32F722") (pin "27") (pinfunction "PB2_27") (pintype "bidirectional"))
    )
    (net (code "64") (name "SPI1_NSS") (class "Default")
      (node (ref "MPU6000") (pin "8") (pinfunction "/CS_8") (pintype "input"))
      (node (ref "STM32F722") (pin "20") (pinfunction "PA4_20") (pintype "bidirectional"))
    )
    (net (code "65") (name "SPI1_SCLK") (class "Default")
      (node (ref "MPU6000") (pin "23") (pinfunction "SCL/SCLK_23") (pintype "input"))
      (node (ref "STM32F722") (pin "51") (pinfunction "PC10_51") (pintype "bidirectional"))
    )
    (net (code "66") (name "SPI2_MISO") (class "Default")
      (node (ref "NRF24L01") (pin "MISO") (pinfunction "MISO_MISO") (pintype "bidirectional"))
      (node (ref "STM32F722") (pin "10") (pinfunction "PC2_10") (pintype "bidirectional"))
    )
    (net (code "67") (name "SPI2_MOSI") (class "Default")
      (node (ref "NRF24L01") (pin "MOSI") (pinfunction "MOSI_MOSI") (pintype "bidirectional"))
      (node (ref "STM32F722") (pin "9") (pinfunction "PC1_9") (pintype "bidirectional"))
    )
    (net (code "68") (name "SPI2_NSS") (class "Default")
      (node (ref "NRF24L01") (pin "CSN") (pinfunction "CSN_CSN") (pintype "bidirectional"))
      (node (ref "STM32F722") (pin "33") (pinfunction "PB12_33") (pintype "bidirectional"))
    )
    (net (code "69") (name "SPI2_SCLK") (class "Default")
      (node (ref "NRF24L01") (pin "SCK") (pinfunction "SCK_SCK") (pintype "bidirectional"))
      (node (ref "STM32F722") (pin "34") (pinfunction "PB13_34") (pintype "bidirectional"))
    )
    (net (code "70") (name "SWCLK") (class "Default")
      (node (ref "JTAG") (pin "2") (pinfunction "2_2") (pintype "passive"))
      (node (ref "STM32F722") (pin "49") (pinfunction "PA14_49") (pintype "bidirectional"))
    )
    (net (code "71") (name "SWDIO") (class "Default")
      (node (ref "JTAG") (pin "4") (pinfunction "4_4") (pintype "passive"))
      (node (ref "STM32F722") (pin "46") (pinfunction "PA13_46") (pintype "bidirectional"))
    )
    (net (code "72") (name "SWO") (class "Default")
      (node (ref "JTAG") (pin "6") (pinfunction "6_6") (pintype "passive"))
      (node (ref "STM32F722") (pin "55") (pinfunction "PB3_55") (pintype "bidirectional"))
    )
    (net (code "73") (name "TRIGG1_IN") (class "Default")
      (node (ref "ATMEGA328P") (pin "30") (pinfunction "PD0(RXD)_30") (pintype "bidirectional"))
      (node (ref "SONIC1") (pin "2") (pinfunction "2_2") (pintype "bidirectional"))
    )
    (net (code "74") (name "TRIGG2_IN") (class "Default")
      (node (ref "ATMEGA328P") (pin "23") (pinfunction "PC0(ADC0)_23") (pintype "bidirectional"))
      (node (ref "SONIC2") (pin "2") (pinfunction "2_2") (pintype "bidirectional"))
    )
    (net (code "75") (name "UART1_RX") (class "Default")
      (node (ref "FT232RL") (pin "1") (pinfunction "TXD_1") (pintype "output"))
      (node (ref "OSD") (pin "3") (pinfunction "3_3") (pintype "bidirectional"))
      (node (ref "STM32F722") (pin "43") (pinfunction "PA10_43") (pintype "bidirectional"))
    )
    (net (code "76") (name "UART1_TX") (class "Default")
      (node (ref "FT232RL") (pin "5") (pinfunction "RXD_5") (pintype "input"))
      (node (ref "OSD") (pin "4") (pinfunction "4_4") (pintype "bidirectional"))
      (node (ref "STM32F722") (pin "42") (pinfunction "PA9_42") (pintype "bidirectional"))
    )
    (net (code "77") (name "UART2_RX") (class "Default")
      (node (ref "GPS") (pin "3") (pinfunction "3_3") (pintype "bidirectional"))
      (node (ref "STM32F722") (pin "17") (pinfunction "PA3_17") (pintype "bidirectional"))
    )
    (net (code "78") (name "UART2_TX") (class "Default")
      (node (ref "GPS") (pin "4") (pinfunction "4_4") (pintype "bidirectional"))
      (node (ref "STM32F722") (pin "16") (pinfunction "PA2_16") (pintype "bidirectional"))
    )
    (net (code "79") (name "USBDM") (class "Default")
      (node (ref "FT232RL") (pin "16") (pinfunction "USBDM_16") (pintype "bidirectional"))
      (node (ref "USB") (pin "D-") (pinfunction "D-_D-") (pintype "bidirectional"))
    )
    (net (code "80") (name "USBDP") (class "Default")
      (node (ref "FT232RL") (pin "15") (pinfunction "USBDP_15") (pintype "bidirectional"))
      (node (ref "USB") (pin "D+") (pinfunction "D+_D+") (pintype "bidirectional"))
    )
    (net (code "81") (name "USBOSD") (class "Default")
      (node (ref "OSD/USB") (pin "2") (pinfunction "2_2") (pintype "passive"))
      (node (ref "STM32F722") (pin "45") (pinfunction "PA12_45") (pintype "bidirectional"))
    )
    (net (code "82") (name "VBAT") (class "Default")
      (node (ref "STM32F722") (pin "1") (pinfunction "VBAT_1") (pintype "power_in"))
    )
    (net (code "83") (name "VCC") (class "Default")
      (node (ref "BMP280") (pin "6") (pinfunction "VDDIO_6") (pintype "power_in"))
      (node (ref "BMP280") (pin "8") (pinfunction "VDD_8") (pintype "power_in"))
      (node (ref "C16") (pin "1") (pinfunction "1_1") (pintype "passive"))
      (node (ref "C17") (pin "1") (pinfunction "1_1") (pintype "passive"))
      (node (ref "C19") (pin "1") (pinfunction "1_1") (pintype "passive"))
      (node (ref "C2") (pin "1") (pinfunction "1_1") (pintype "passive"))
      (node (ref "C20") (pin "1") (pinfunction "1_1") (pintype "passive"))
      (node (ref "C22") (pin "1") (pinfunction "1_1") (pintype "passive"))
      (node (ref "C25") (pin "2") (pinfunction "2_2") (pintype "passive"))
      (node (ref "C27") (pin "1") (pinfunction "1_1") (pintype "passive"))
      (node (ref "C29") (pin "2") (pinfunction "2_2") (pintype "passive"))
      (node (ref "C3") (pin "1") (pinfunction "1_1") (pintype "passive"))
      (node (ref "C32") (pin "1") (pinfunction "1_1") (pintype "passive"))
      (node (ref "C33") (pin "1") (pinfunction "1_1") (pintype "passive"))
      (node (ref "C37") (pin "2") (pinfunction "2_2") (pintype "passive"))
      (node (ref "C38") (pin "2") (pinfunction "2_2") (pintype "passive"))
      (node (ref "C4") (pin "1") (pinfunction "1_1") (pintype "passive"))
      (node (ref "C5") (pin "1") (pinfunction "1_1") (pintype "passive"))
      (node (ref "C6") (pin "1") (pinfunction "1_1") (pintype "passive"))
      (node (ref "C7") (pin "1") (pinfunction "1_1") (pintype "passive"))
      (node (ref "DAC") (pin "2") (pinfunction "2_2") (pintype "passive"))
      (node (ref "FT232RL") (pin "4") (pinfunction "VCCIO_4") (pintype "power_in"))
      (node (ref "GIMBAL_X") (pin "2") (pinfunction "2_2") (pintype "passive"))
      (node (ref "GIMBAL_Y") (pin "2") (pinfunction "2_2") (pintype "passive"))
      (node (ref "GIMBAL_Z") (pin "2") (pinfunction "2_2") (pintype "passive"))
      (node (ref "GPS") (pin "1") (pinfunction "1_1") (pintype "bidirectional"))
      (node (ref "GY87") (pin "7") (pinfunction "7_7") (pintype "passive"))
      (node (ref "JTAG") (pin "1") (pinfunction "1_1") (pintype "passive"))
      (node (ref "LED6") (pin "A") (pinfunction "A_A") (pintype "passive"))
      (node (ref "LM3940-3.3") (pin "3") (pinfunction "OUT_3") (pintype "output"))
      (node (ref "MPU6000") (pin "13") (pinfunction "VDD_13") (pintype "power_in"))
      (node (ref "NRF24L01") (pin "VCC") (pinfunction "VCC_VCC") (pintype "power_in"))
      (node (ref "OSD") (pin "1") (pinfunction "1_1") (pintype "bidirectional"))
      (node (ref "OSD/USB") (pin "1") (pinfunction "1_1") (pintype "passive"))
      (node (ref "R13") (pin "2") (pinfunction "2_2") (pintype "passive"))
      (node (ref "R2") (pin "2") (pinfunction "2_2") (pintype "passive"))
      (node (ref "R3") (pin "2") (pinfunction "2_2") (pintype "passive"))
      (node (ref "R4") (pin "2") (pinfunction "2_2") (pintype "passive"))
      (node (ref "R5") (pin "2") (pinfunction "2_2") (pintype "passive"))
      (node (ref "SD_CARD") (pin "4") (pinfunction "VDD_4") (pintype "power_in"))
      (node (ref "STM32F722") (pin "13") (pinfunction "VDDA_13") (pintype "power_in"))
      (node (ref "STM32F722") (pin "19") (pinfunction "VDD_2_19") (pintype "power_in"))
      (node (ref "STM32F722") (pin "32") (pinfunction "VDD_3_32") (pintype "power_in"))
      (node (ref "STM32F722") (pin "48") (pinfunction "VDD_4_48") (pintype "power_in"))
      (node (ref "STM32F722") (pin "64") (pinfunction "VDD_64") (pintype "power_in"))
      (node (ref "TXB0104") (pin "1") (pinfunction "VCCA_1") (pintype "bidirectional"))
    )
    (net (code "84") (name "VCC_2") (class "Default")
      (node (ref "ADC1") (pin "2") (pinfunction "2_2") (pintype "passive"))
      (node (ref "ADC2") (pin "2") (pinfunction "2_2") (pintype "passive"))
      (node (ref "ATMEGA328P") (pin "18") (pinfunction "AVCC_18") (pintype "bidirectional"))
      (node (ref "ATMEGA328P") (pin "4") (pinfunction "VCC_4") (pintype "bidirectional"))
      (node (ref "ATMEGA328P") (pin "6") (pinfunction "VCC_6") (pintype "bidirectional"))
      (node (ref "C13") (pin "1") (pinfunction "1_1") (pintype "passive"))
      (node (ref "C14") (pin "1") (pinfunction "1_1") (pintype "passive"))
      (node (ref "C15") (pin "1") (pinfunction "1_1") (pintype "passive"))
      (node (ref "C18") (pin "1") (pinfunction "1_1") (pintype "passive"))
      (node (ref "C21") (pin "1") (pinfunction "1_1") (pintype "passive"))
      (node (ref "C23") (pin "1") (pinfunction "1_1") (pintype "passive"))
      (node (ref "C28") (pin "2") (pinfunction "2_2") (pintype "passive"))
      (node (ref "C34") (pin "1") (pinfunction "1_1") (pintype "passive"))
      (node (ref "D1") (pin "C") (pinfunction "C_C") (pintype "passive"))
      (node (ref "FT232RL") (pin "20") (pinfunction "VCC_20") (pintype "power_in"))
      (node (ref "ICSP") (pin "2") (pinfunction "VCC_2") (pintype "power_in"))
      (node (ref "LED") (pin "1") (pinfunction "1_1") (pintype "passive"))
      (node (ref "LED1") (pin "A") (pinfunction "A_A") (pintype "passive"))
      (node (ref "LED2") (pin "A") (pinfunction "A_A") (pintype "passive"))
      (node (ref "LM3940-3.3") (pin "1") (pinfunction "IN_1") (pintype "power_in"))
      (node (ref "M1") (pin "2") (pinfunction "2_2") (pintype "passive"))
      (node (ref "M2") (pin "2") (pinfunction "2_2") (pintype "passive"))
      (node (ref "M3") (pin "2") (pinfunction "2_2") (pintype "passive"))
      (node (ref "M4") (pin "2") (pinfunction "2_2") (pintype "passive"))
      (node (ref "PPM") (pin "2") (pinfunction "2_2") (pintype "passive"))
      (node (ref "SONIC1") (pin "1") (pinfunction "1_1") (pintype "bidirectional"))
      (node (ref "SONIC2") (pin "1") (pinfunction "1_1") (pintype "bidirectional"))
      (node (ref "TXB0104") (pin "14") (pinfunction "VCCB_14") (pintype "bidirectional"))
    )
    (net (code "85") (name "V_USB") (class "Default")
      (node (ref "D1") (pin "A") (pinfunction "A_A") (pintype "passive"))
      (node (ref "USB") (pin "VBUS") (pinfunction "VBUS_VBUS") (pintype "power_in"))
    )
    (net (code "86") (name "unconnected-(ATMEGA328P-PB0(ICP)-Pad12)") (class "Default")
      (node (ref "ATMEGA328P") (pin "12") (pinfunction "PB0(ICP)_12") (pintype "bidirectional"))
    )
    (net (code "87") (name "unconnected-(ATMEGA328P-PC2(ADC2)-Pad25)") (class "Default")
      (node (ref "ATMEGA328P") (pin "25") (pinfunction "PC2(ADC2)_25") (pintype "bidirectional"))
    )
    (net (code "88") (name "unconnected-(ATMEGA328P-PC3(ADC3)-Pad26)") (class "Default")
      (node (ref "ATMEGA328P") (pin "26") (pinfunction "PC3(ADC3)_26") (pintype "bidirectional"))
    )
    (net (code "89") (name "unconnected-(ATMEGA328P-PD3(INT1)-Pad1)") (class "Default")
      (node (ref "ATMEGA328P") (pin "1") (pinfunction "PD3(INT1)_1") (pintype "bidirectional"))
    )
    (net (code "90") (name "unconnected-(ATMEGA328P-PD4(XCK{slash}T0)-Pad2)") (class "Default")
      (node (ref "ATMEGA328P") (pin "2") (pinfunction "PD4(XCK/T0)_2") (pintype "bidirectional"))
    )
    (net (code "91") (name "unconnected-(ATMEGA328P-PD5(T1)-Pad9)") (class "Default")
      (node (ref "ATMEGA328P") (pin "9") (pinfunction "PD5(T1)_9") (pintype "bidirectional"))
    )
    (net (code "92") (name "unconnected-(ATMEGA328P-PD6(AIN0)-Pad10)") (class "Default")
      (node (ref "ATMEGA328P") (pin "10") (pinfunction "PD6(AIN0)_10") (pintype "bidirectional"))
    )
    (net (code "93") (name "unconnected-(ATMEGA328P-PD7(AIN1)-Pad11)") (class "Default")
      (node (ref "ATMEGA328P") (pin "11") (pinfunction "PD7(AIN1)_11") (pintype "bidirectional"))
    )
    (net (code "94") (name "unconnected-(FT232RL-CBUS2-Pad13)") (class "Default")
      (node (ref "FT232RL") (pin "13") (pinfunction "CBUS2_13") (pintype "bidirectional"))
    )
    (net (code "95") (name "unconnected-(FT232RL-CBUS3-Pad14)") (class "Default")
      (node (ref "FT232RL") (pin "14") (pinfunction "CBUS3_14") (pintype "bidirectional"))
    )
    (net (code "96") (name "unconnected-(FT232RL-CBUS4-Pad12)") (class "Default")
      (node (ref "FT232RL") (pin "12") (pinfunction "CBUS4_12") (pintype "bidirectional"))
    )
    (net (code "97") (name "unconnected-(FT232RL-OSCI-Pad27)") (class "Default")
      (node (ref "FT232RL") (pin "27") (pinfunction "OSCI_27") (pintype "input"))
    )
    (net (code "98") (name "unconnected-(FT232RL-OSCO-Pad28)") (class "Default")
      (node (ref "FT232RL") (pin "28") (pinfunction "OSCO_28") (pintype "output"))
    )
    (net (code "99") (name "unconnected-(FT232RL-~{CTS}-Pad11)") (class "Default")
      (node (ref "FT232RL") (pin "11") (pinfunction "~{CTS}_11") (pintype "input"))
    )
    (net (code "100") (name "unconnected-(FT232RL-~{DCD}-Pad10)") (class "Default")
      (node (ref "FT232RL") (pin "10") (pinfunction "~{DCD}_10") (pintype "input"))
    )
    (net (code "101") (name "unconnected-(FT232RL-~{DSR}-Pad9)") (class "Default")
      (node (ref "FT232RL") (pin "9") (pinfunction "~{DSR}_9") (pintype "input"))
    )
    (net (code "102") (name "unconnected-(FT232RL-~{RESET}-Pad19)") (class "Default")
      (node (ref "FT232RL") (pin "19") (pinfunction "~{RESET}_19") (pintype "input"))
    )
    (net (code "103") (name "unconnected-(FT232RL-~{RI}-Pad6)") (class "Default")
      (node (ref "FT232RL") (pin "6") (pinfunction "~{RI}_6") (pintype "input"))
    )
    (net (code "104") (name "unconnected-(FT232RL-~{RTS}-Pad3)") (class "Default")
      (node (ref "FT232RL") (pin "3") (pinfunction "~{RTS}_3") (pintype "output"))
    )
    (net (code "105") (name "unconnected-(GY87-Pad8)") (class "Default")
      (node (ref "GY87") (pin "8") (pinfunction "8_8") (pintype "passive"))
    )
    (net (code "106") (name "unconnected-(JP1-Pad1)") (class "Default")
      (node (ref "JP1") (pin "1") (pinfunction "1_1") (pintype "passive"))
    )
    (net (code "107") (name "unconnected-(JP1-Pad2)") (class "Default")
      (node (ref "JP1") (pin "2") (pinfunction "2_2") (pintype "passive"))
    )
    (net (code "108") (name "unconnected-(JP1-Pad3)") (class "Default")
      (node (ref "JP1") (pin "3") (pinfunction "3_3") (pintype "passive"))
    )
    (net (code "109") (name "unconnected-(JP1-Pad4)") (class "Default")
      (node (ref "JP1") (pin "4") (pinfunction "4_4") (pintype "passive"))
    )
    (net (code "110") (name "unconnected-(JP1-Pad5)") (class "Default")
      (node (ref "JP1") (pin "5") (pinfunction "5_5") (pintype "passive"))
    )
    (net (code "111") (name "unconnected-(JP1-Pad6)") (class "Default")
      (node (ref "JP1") (pin "6") (pinfunction "6_6") (pintype "passive"))
    )
    (net (code "112") (name "unconnected-(JP2-Pad1)") (class "Default")
      (node (ref "JP2") (pin "1") (pinfunction "1_1") (pintype "passive"))
    )
    (net (code "113") (name "unconnected-(JP2-Pad2)") (class "Default")
      (node (ref "JP2") (pin "2") (pinfunction "2_2") (pintype "passive"))
    )
    (net (code "114") (name "unconnected-(JP2-Pad3)") (class "Default")
      (node (ref "JP2") (pin "3") (pinfunction "3_3") (pintype "passive"))
    )
    (net (code "115") (name "unconnected-(JP2-Pad4)") (class "Default")
      (node (ref "JP2") (pin "4") (pinfunction "4_4") (pintype "passive"))
    )
    (net (code "116") (name "unconnected-(JP2-Pad5)") (class "Default")
      (node (ref "JP2") (pin "5") (pinfunction "5_5") (pintype "passive"))
    )
    (net (code "117") (name "unconnected-(JP2-Pad6)") (class "Default")
      (node (ref "JP2") (pin "6") (pinfunction "6_6") (pintype "passive"))
    )
    (net (code "118") (name "unconnected-(JP3-Pad1)") (class "Default")
      (node (ref "JP3") (pin "1") (pinfunction "1_1") (pintype "passive"))
    )
    (net (code "119") (name "unconnected-(JP3-Pad2)") (class "Default")
      (node (ref "JP3") (pin "2") (pinfunction "2_2") (pintype "passive"))
    )
    (net (code "120") (name "unconnected-(JP3-Pad3)") (class "Default")
      (node (ref "JP3") (pin "3") (pinfunction "3_3") (pintype "passive"))
    )
    (net (code "121") (name "unconnected-(JP3-Pad4)") (class "Default")
      (node (ref "JP3") (pin "4") (pinfunction "4_4") (pintype "passive"))
    )
    (net (code "122") (name "unconnected-(JP3-Pad5)") (class "Default")
      (node (ref "JP3") (pin "5") (pinfunction "5_5") (pintype "passive"))
    )
    (net (code "123") (name "unconnected-(JP3-Pad6)") (class "Default")
      (node (ref "JP3") (pin "6") (pinfunction "6_6") (pintype "passive"))
    )
    (net (code "124") (name "unconnected-(JP4-Pad1)") (class "Default")
      (node (ref "JP4") (pin "1") (pinfunction "1_1") (pintype "passive"))
    )
    (net (code "125") (name "unconnected-(JP4-Pad2)") (class "Default")
      (node (ref "JP4") (pin "2") (pinfunction "2_2") (pintype "passive"))
    )
    (net (code "126") (name "unconnected-(JP4-Pad3)") (class "Default")
      (node (ref "JP4") (pin "3") (pinfunction "3_3") (pintype "passive"))
    )
    (net (code "127") (name "unconnected-(JP4-Pad4)") (class "Default")
      (node (ref "JP4") (pin "4") (pinfunction "4_4") (pintype "passive"))
    )
    (net (code "128") (name "unconnected-(JP4-Pad5)") (class "Default")
      (node (ref "JP4") (pin "5") (pinfunction "5_5") (pintype "passive"))
    )
    (net (code "129") (name "unconnected-(JP4-Pad6)") (class "Default")
      (node (ref "JP4") (pin "6") (pinfunction "6_6") (pintype "passive"))
    )
    (net (code "130") (name "unconnected-(JP5-Pad1)") (class "Default")
      (node (ref "JP5") (pin "1") (pinfunction "1_1") (pintype "passive"))
    )
    (net (code "131") (name "unconnected-(JP5-Pad2)") (class "Default")
      (node (ref "JP5") (pin "2") (pinfunction "2_2") (pintype "passive"))
    )
    (net (code "132") (name "unconnected-(JP5-Pad3)") (class "Default")
      (node (ref "JP5") (pin "3") (pinfunction "3_3") (pintype "passive"))
    )
    (net (code "133") (name "unconnected-(JP5-Pad4)") (class "Default")
      (node (ref "JP5") (pin "4") (pinfunction "4_4") (pintype "passive"))
    )
    (net (code "134") (name "unconnected-(JP5-Pad5)") (class "Default")
      (node (ref "JP5") (pin "5") (pinfunction "5_5") (pintype "passive"))
    )
    (net (code "135") (name "unconnected-(JP5-Pad6)") (class "Default")
      (node (ref "JP5") (pin "6") (pinfunction "6_6") (pintype "passive"))
    )
    (net (code "136") (name "unconnected-(JP6-Pad1)") (class "Default")
      (node (ref "JP6") (pin "1") (pinfunction "1_1") (pintype "passive"))
    )
    (net (code "137") (name "unconnected-(JP6-Pad2)") (class "Default")
      (node (ref "JP6") (pin "2") (pinfunction "2_2") (pintype "passive"))
    )
    (net (code "138") (name "unconnected-(JP6-Pad3)") (class "Default")
      (node (ref "JP6") (pin "3") (pinfunction "3_3") (pintype "passive"))
    )
    (net (code "139") (name "unconnected-(JP6-Pad4)") (class "Default")
      (node (ref "JP6") (pin "4") (pinfunction "4_4") (pintype "passive"))
    )
    (net (code "140") (name "unconnected-(JP6-Pad5)") (class "Default")
      (node (ref "JP6") (pin "5") (pinfunction "5_5") (pintype "passive"))
    )
    (net (code "141") (name "unconnected-(JP6-Pad6)") (class "Default")
      (node (ref "JP6") (pin "6") (pinfunction "6_6") (pintype "passive"))
    )
    (net (code "142") (name "unconnected-(JP7-Pad1)") (class "Default")
      (node (ref "JP7") (pin "1") (pinfunction "1_1") (pintype "passive"))
    )
    (net (code "143") (name "unconnected-(JP7-Pad2)") (class "Default")
      (node (ref "JP7") (pin "2") (pinfunction "2_2") (pintype "passive"))
    )
    (net (code "144") (name "unconnected-(JP7-Pad3)") (class "Default")
      (node (ref "JP7") (pin "3") (pinfunction "3_3") (pintype "passive"))
    )
    (net (code "145") (name "unconnected-(JP7-Pad4)") (class "Default")
      (node (ref "JP7") (pin "4") (pinfunction "4_4") (pintype "passive"))
    )
    (net (code "146") (name "unconnected-(JP7-Pad5)") (class "Default")
      (node (ref "JP7") (pin "5") (pinfunction "5_5") (pintype "passive"))
    )
    (net (code "147") (name "unconnected-(JP7-Pad6)") (class "Default")
      (node (ref "JP7") (pin "6") (pinfunction "6_6") (pintype "passive"))
    )
    (net (code "148") (name "unconnected-(MPU6000A-AUX_CL-Pad7)") (class "Default")
      (node (ref "MPU6000") (pin "7") (pinfunction "AUX_CL_7") (pintype "bidirectional"))
    )
    (net (code "149") (name "unconnected-(MPU6000A-AUX_DA-Pad6)") (class "Default")
      (node (ref "MPU6000") (pin "6") (pinfunction "AUX_DA_6") (pintype "bidirectional"))
    )
    (net (code "150") (name "unconnected-(MPU6000A-GND-Pad25)") (class "Default")
      (node (ref "MPU6000") (pin "25") (pinfunction "GND_25") (pintype "power_in"))
    )
    (net (code "151") (name "unconnected-(MPU6000A-RESV-Pad19)") (class "Default")
      (node (ref "MPU6000") (pin "19") (pinfunction "RESV_19") (pintype "passive"))
    )
    (net (code "152") (name "unconnected-(MPU6000A-RESV-Pad21)") (class "Default")
      (node (ref "MPU6000") (pin "21") (pinfunction "RESV_21") (pintype "passive"))
    )
    (net (code "153") (name "unconnected-(MPU6000A-RESV-Pad22)") (class "Default")
      (node (ref "MPU6000") (pin "22") (pinfunction "RESV_22") (pintype "passive"))
    )
    (net (code "154") (name "unconnected-(SD_CARD-DAT1-Pad8)") (class "Default")
      (node (ref "SD_CARD") (pin "8") (pinfunction "DAT1_8") (pintype "bidirectional"))
    )
    (net (code "155") (name "unconnected-(SD_CARD-DAT2-Pad1)") (class "Default")
      (node (ref "SD_CARD") (pin "1") (pinfunction "DAT2_1") (pintype "bidirectional"))
    )
    (net (code "156") (name "unconnected-(SD_CARD-DAT3{slash}CD-Pad2)") (class "Default")
      (node (ref "SD_CARD") (pin "2") (pinfunction "DAT3/CD_2") (pintype "bidirectional"))
    )
    (net (code "157") (name "unconnected-(STM32F722A-PA15-Pad50)") (class "Default")
      (node (ref "STM32F722") (pin "50") (pinfunction "PA15_50") (pintype "bidirectional"))
    )
    (net (code "158") (name "unconnected-(STM32F722A-PB14-Pad35)") (class "Default")
      (node (ref "STM32F722") (pin "35") (pinfunction "PB14_35") (pintype "bidirectional"))
    )
    (net (code "159") (name "unconnected-(STM32F722A-PB15-Pad36)") (class "Default")
      (node (ref "STM32F722") (pin "36") (pinfunction "PB15_36") (pintype "bidirectional"))
    )
    (net (code "160") (name "unconnected-(STM32F722A-PC0-Pad8)") (class "Default")
      (node (ref "STM32F722") (pin "8") (pinfunction "PC0_8") (pintype "bidirectional"))
    )
    (net (code "161") (name "unconnected-(STM32F722A-PC3-Pad11)") (class "Default")
      (node (ref "STM32F722") (pin "11") (pinfunction "PC3_11") (pintype "bidirectional"))
    )
    (net (code "162") (name "unconnected-(STM32F722A-PC13-Pad2)") (class "Default")
      (node (ref "STM32F722") (pin "2") (pinfunction "PC13_2") (pintype "bidirectional"))
    )
    (net (code "163") (name "unconnected-(STM32F722A-PC14-OSC32_IN-Pad3)") (class "Default")
      (node (ref "STM32F722") (pin "3") (pinfunction "PC14-OSC32_IN_3") (pintype "bidirectional"))
    )
    (net (code "164") (name "unconnected-(STM32F722A-PC15-OSC32_OUT-Pad4)") (class "Default")
      (node (ref "STM32F722") (pin "4") (pinfunction "PC15-OSC32_OUT_4") (pintype "bidirectional"))
    )
    (net (code "165") (name "unconnected-(USB-PadID)") (class "Default")
      (node (ref "USB") (pin "ID") (pinfunction "ID_ID") (pintype "bidirectional"))
    )
  )
)
